# 4-Flowmeter.net
KiCad netlist of a schematic drawn in EAGLE
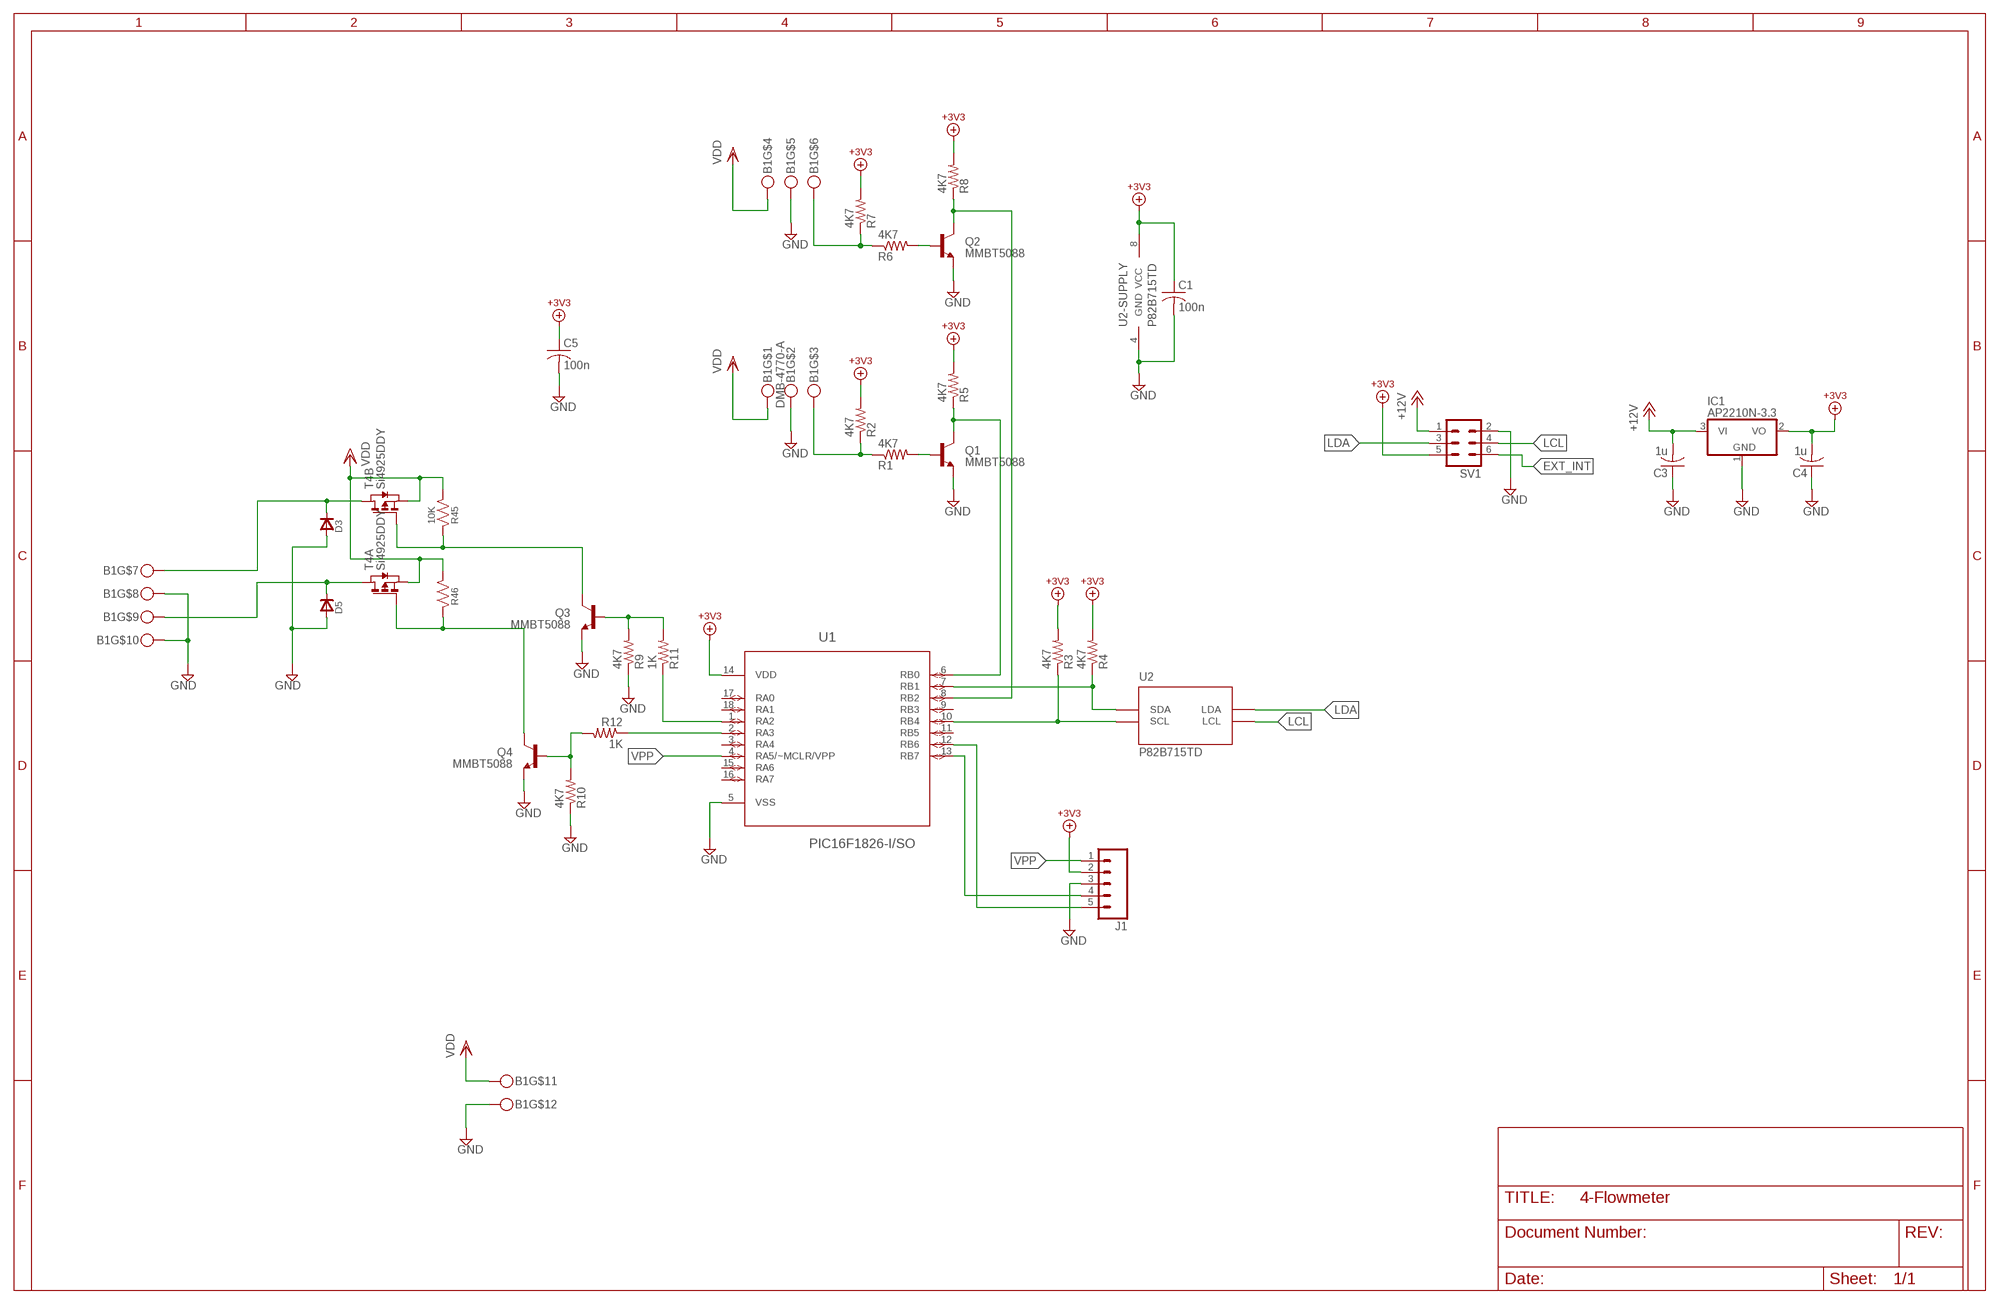
[diagram p0: schematic, sheet 1]

(export (version "E")
  (design (tool "Eeschema 10.0.6"))
  (components
    (comp (ref "B1")
      (value "DMB-4770-A")
      (footprint "eagle-import:DMB-4770-A-PKG")
      (libsource (lib "eagle-import") (part "DMB-4770-A"))
    )
    (comp (ref "C1")
      (value "100n")
      (footprint "eagle-import:C0805")
      (libsource (lib "eagle-import") (part "C-USC0805"))
    )
    (comp (ref "C3")
      (value "1u")
      (footprint "eagle-import:C0805")
      (libsource (lib "eagle-import") (part "C-USC0805"))
    )
    (comp (ref "C4")
      (value "1u")
      (footprint "eagle-import:C0805")
      (libsource (lib "eagle-import") (part "C-USC0805"))
    )
    (comp (ref "C5")
      (value "100n")
      (footprint "eagle-import:C0805")
      (libsource (lib "eagle-import") (part "C-USC0805"))
    )
    (comp (ref "D3")
      (value "DSMA")
      (footprint "eagle-import:DSMA")
      (libsource (lib "eagle-import") (part "DSMA"))
    )
    (comp (ref "D5")
      (value "DSMA")
      (footprint "eagle-import:DSMA")
      (libsource (lib "eagle-import") (part "DSMA"))
    )
    (comp (ref "IC1")
      (value "AP2210N-3.3")
      (footprint "eagle-import:SOT23")
      (libsource (lib "eagle-import") (part "MCP1703CB"))
    )
    (comp (ref "J1")
      (value "M05PTH")
      (footprint "eagle-import:1X05")
      (libsource (lib "eagle-import") (part "M05PTH"))
    )
    (comp (ref "Q1")
      (value "MMBT5088")
      (footprint "eagle-import:SOT23-3")
      (libsource (lib "eagle-import") (part "TRANSISTOR_NPNMMBT5088"))
    )
    (comp (ref "Q2")
      (value "MMBT5088")
      (footprint "eagle-import:SOT23-3")
      (libsource (lib "eagle-import") (part "TRANSISTOR_NPNMMBT5088"))
    )
    (comp (ref "Q3")
      (value "MMBT5088")
      (footprint "eagle-import:SOT23-3")
      (libsource (lib "eagle-import") (part "TRANSISTOR_NPNMMBT5088"))
    )
    (comp (ref "Q4")
      (value "MMBT5088")
      (footprint "eagle-import:SOT23-3")
      (libsource (lib "eagle-import") (part "TRANSISTOR_NPNMMBT5088"))
    )
    (comp (ref "R1")
      (value "4K7")
      (footprint "eagle-import:R0805")
      (libsource (lib "eagle-import") (part "R-US_R0805"))
    )
    (comp (ref "R2")
      (value "4K7")
      (footprint "eagle-import:R0805")
      (libsource (lib "eagle-import") (part "R-US_R0805"))
    )
    (comp (ref "R3")
      (value "4K7")
      (footprint "eagle-import:R0805")
      (libsource (lib "eagle-import") (part "R-US_R0805"))
    )
    (comp (ref "R4")
      (value "4K7")
      (footprint "eagle-import:R0805")
      (libsource (lib "eagle-import") (part "R-US_R0805"))
    )
    (comp (ref "R5")
      (value "4K7")
      (footprint "eagle-import:R0805")
      (libsource (lib "eagle-import") (part "R-US_R0805"))
    )
    (comp (ref "R6")
      (value "4K7")
      (footprint "eagle-import:R0805")
      (libsource (lib "eagle-import") (part "R-US_R0805"))
    )
    (comp (ref "R7")
      (value "4K7")
      (footprint "eagle-import:R0805")
      (libsource (lib "eagle-import") (part "R-US_R0805"))
    )
    (comp (ref "R8")
      (value "4K7")
      (footprint "eagle-import:R0805")
      (libsource (lib "eagle-import") (part "R-US_R0805"))
    )
    (comp (ref "R9")
      (value "4K7")
      (footprint "eagle-import:R0805")
      (libsource (lib "eagle-import") (part "R-US_R0805"))
    )
    (comp (ref "R10")
      (value "4K7")
      (footprint "eagle-import:R0805")
      (libsource (lib "eagle-import") (part "R-US_R0805"))
    )
    (comp (ref "R11")
      (value "1K")
      (footprint "eagle-import:R0805")
      (libsource (lib "eagle-import") (part "R-US_R0805"))
    )
    (comp (ref "R12")
      (value "1K")
      (footprint "eagle-import:R0805")
      (libsource (lib "eagle-import") (part "R-US_R0805"))
    )
    (comp (ref "R45")
      (value "10K")
      (footprint "eagle-import:R0805")
      (libsource (lib "eagle-import") (part "RU0805"))
    )
    (comp (ref "R46")
      (value "RU0805")
      (footprint "eagle-import:R0805")
      (libsource (lib "eagle-import") (part "RU0805"))
    )
    (comp (ref "SV1")
      (value "ML6")
      (footprint "eagle-import:ML6")
      (libsource (lib "eagle-import") (part "ML6"))
    )
    (comp (ref "T4")
      (value "Si4925DDY")
      (footprint "eagle-import:SO8")
      (libsource (lib "eagle-import") (part "PMOS2SO8"))
    )
    (comp (ref "U1")
      (value "PIC16F1826-I/SO")
      (footprint "eagle-import:SOIC127P1030X175-18N")
      (libsource (lib "eagle-import") (part "PIC16F1826-I/SO"))
    )
    (comp (ref "U2")
      (value "P82B715TD")
      (footprint "eagle-import:SOIC-8")
      (fields (field (name "MANUFACTURER") "NXP Semiconductors") (field (name "PART_NUMBER") "P82B715TD,118"))
      (libsource (lib "eagle-import") (part "P82B715?TD"))
    )
  )
  (nets
    (net (code "1") (name "+12V") (class "Default")
      (node (ref "C3") (pin "2") (pinfunction "2_2") (pintype "passive"))
      (node (ref "IC1") (pin "3") (pinfunction "VI_3") (pintype "input"))
      (node (ref "SV1") (pin "1") (pinfunction "1_1") (pintype "passive"))
    )
    (net (code "2") (name "EXT_INT") (class "Default")
      (node (ref "SV1") (pin "6") (pinfunction "6_6") (pintype "passive"))
    )
    (net (code "3") (name "GND") (class "Default")
      (node (ref "B1") (pin "P$10") (pinfunction "KL_P$10") (pintype "passive"))
      (node (ref "B1") (pin "P$12") (pinfunction "KL_P$12") (pintype "passive"))
      (node (ref "B1") (pin "P$2") (pinfunction "KL_P$2") (pintype "passive"))
      (node (ref "B1") (pin "P$5") (pinfunction "KL_P$5") (pintype "passive"))
      (node (ref "B1") (pin "P$8") (pinfunction "KL_P$8") (pintype "passive"))
      (node (ref "C1") (pin "2") (pinfunction "2_2") (pintype "passive"))
      (node (ref "C3") (pin "1") (pinfunction "1_1") (pintype "passive"))
      (node (ref "C4") (pin "1") (pinfunction "1_1") (pintype "passive"))
      (node (ref "C5") (pin "2") (pinfunction "2_2") (pintype "passive"))
      (node (ref "D3") (pin "A") (pinfunction "A_A") (pintype "passive"))
      (node (ref "D5") (pin "A") (pinfunction "A_A") (pintype "passive"))
      (node (ref "IC1") (pin "1") (pinfunction "GND_1") (pintype "passive"))
      (node (ref "J1") (pin "3") (pinfunction "3_3") (pintype "passive"))
      (node (ref "Q1") (pin "2") (pinfunction "E_2") (pintype "passive"))
      (node (ref "Q2") (pin "2") (pinfunction "E_2") (pintype "passive"))
      (node (ref "Q3") (pin "2") (pinfunction "E_2") (pintype "passive"))
      (node (ref "Q4") (pin "2") (pinfunction "E_2") (pintype "passive"))
      (node (ref "R10") (pin "1") (pinfunction "1_1") (pintype "passive"))
      (node (ref "R9") (pin "1") (pinfunction "1_1") (pintype "passive"))
      (node (ref "SV1") (pin "2") (pinfunction "2_2") (pintype "passive"))
      (node (ref "U1") (pin "5") (pinfunction "VSS_5") (pintype "power_in"))
      (node (ref "U2") (pin "4") (pinfunction "GND_4") (pintype "bidirectional"))
    )
    (net (code "4") (name "LCL") (class "Default")
      (node (ref "SV1") (pin "4") (pinfunction "4_4") (pintype "passive"))
      (node (ref "U2") (pin "2") (pinfunction "LCL_2") (pintype "bidirectional"))
    )
    (net (code "5") (name "LDA") (class "Default")
      (node (ref "SV1") (pin "3") (pinfunction "3_3") (pintype "passive"))
      (node (ref "U2") (pin "7") (pinfunction "LDA_7") (pintype "bidirectional"))
    )
    (net (code "6") (name "Net-(B1F-KL)") (class "Default")
      (node (ref "B1") (pin "P$3") (pinfunction "KL_P$3") (pintype "passive"))
      (node (ref "R1") (pin "1") (pinfunction "1_1") (pintype "passive"))
      (node (ref "R2") (pin "1") (pinfunction "1_1") (pintype "passive"))
    )
    (net (code "7") (name "Net-(B1I-KL)") (class "Default")
      (node (ref "B1") (pin "P$6") (pinfunction "KL_P$6") (pintype "passive"))
      (node (ref "R6") (pin "1") (pinfunction "1_1") (pintype "passive"))
      (node (ref "R7") (pin "1") (pinfunction "1_1") (pintype "passive"))
    )
    (net (code "8") (name "Net-(B1J-KL)") (class "Default")
      (node (ref "B1") (pin "P$7") (pinfunction "KL_P$7") (pintype "passive"))
      (node (ref "D3") (pin "C") (pinfunction "C_C") (pintype "passive"))
      (node (ref "T4") (pin "5") (pinfunction "D_5") (pintype "passive"))
      (node (ref "T4") (pin "6") (pinfunction "D_6") (pintype "passive"))
    )
    (net (code "9") (name "Net-(B1L-KL)") (class "Default")
      (node (ref "B1") (pin "P$9") (pinfunction "KL_P$9") (pintype "passive"))
      (node (ref "D5") (pin "C") (pinfunction "C_C") (pintype "passive"))
      (node (ref "T4") (pin "7") (pinfunction "D_7") (pintype "passive"))
      (node (ref "T4") (pin "8") (pinfunction "D_8") (pintype "passive"))
    )
    (net (code "10") (name "Net-(Q1-B)") (class "Default")
      (node (ref "Q1") (pin "1") (pinfunction "B_1") (pintype "passive"))
      (node (ref "R1") (pin "2") (pinfunction "2_2") (pintype "passive"))
    )
    (net (code "11") (name "Net-(Q1-C)") (class "Default")
      (node (ref "Q1") (pin "3") (pinfunction "C_3") (pintype "passive"))
      (node (ref "R5") (pin "1") (pinfunction "1_1") (pintype "passive"))
      (node (ref "U1") (pin "6") (pinfunction "RB0_6") (pintype "bidirectional"))
    )
    (net (code "12") (name "Net-(Q2-B)") (class "Default")
      (node (ref "Q2") (pin "1") (pinfunction "B_1") (pintype "passive"))
      (node (ref "R6") (pin "2") (pinfunction "2_2") (pintype "passive"))
    )
    (net (code "13") (name "Net-(Q2-C)") (class "Default")
      (node (ref "Q2") (pin "3") (pinfunction "C_3") (pintype "passive"))
      (node (ref "R8") (pin "1") (pinfunction "1_1") (pintype "passive"))
      (node (ref "U1") (pin "8") (pinfunction "RB2_8") (pintype "bidirectional"))
    )
    (net (code "14") (name "Net-(Q3-B)") (class "Default")
      (node (ref "Q3") (pin "1") (pinfunction "B_1") (pintype "passive"))
      (node (ref "R11") (pin "2") (pinfunction "2_2") (pintype "passive"))
      (node (ref "R9") (pin "2") (pinfunction "2_2") (pintype "passive"))
    )
    (net (code "15") (name "Net-(Q3-C)") (class "Default")
      (node (ref "Q3") (pin "3") (pinfunction "C_3") (pintype "passive"))
      (node (ref "R45") (pin "1") (pinfunction "1_1") (pintype "passive"))
      (node (ref "T4") (pin "4") (pinfunction "G_4") (pintype "passive"))
    )
    (net (code "16") (name "Net-(Q4-B)") (class "Default")
      (node (ref "Q4") (pin "1") (pinfunction "B_1") (pintype "passive"))
      (node (ref "R10") (pin "2") (pinfunction "2_2") (pintype "passive"))
      (node (ref "R12") (pin "2") (pinfunction "2_2") (pintype "passive"))
    )
    (net (code "17") (name "Net-(Q4-C)") (class "Default")
      (node (ref "Q4") (pin "3") (pinfunction "C_3") (pintype "passive"))
      (node (ref "R46") (pin "1") (pinfunction "1_1") (pintype "passive"))
      (node (ref "T4") (pin "2") (pinfunction "G_2") (pintype "passive"))
    )
    (net (code "18") (name "Net-(U1-RA2)") (class "Default")
      (node (ref "R11") (pin "1") (pinfunction "1_1") (pintype "passive"))
      (node (ref "U1") (pin "1") (pinfunction "RA2_1") (pintype "bidirectional"))
    )
    (net (code "19") (name "Net-(U1-RA3)") (class "Default")
      (node (ref "R12") (pin "1") (pinfunction "1_1") (pintype "passive"))
      (node (ref "U1") (pin "2") (pinfunction "RA3_2") (pintype "bidirectional"))
    )
    (net (code "20") (name "Net-(U1-RB1)") (class "Default")
      (node (ref "R4") (pin "1") (pinfunction "1_1") (pintype "passive"))
      (node (ref "U1") (pin "7") (pinfunction "RB1_7") (pintype "bidirectional"))
      (node (ref "U2") (pin "6") (pinfunction "SDA_6") (pintype "bidirectional"))
    )
    (net (code "21") (name "Net-(U1-RB4)") (class "Default")
      (node (ref "R3") (pin "1") (pinfunction "1_1") (pintype "passive"))
      (node (ref "U1") (pin "10") (pinfunction "RB4_10") (pintype "bidirectional"))
      (node (ref "U2") (pin "3") (pinfunction "SCL_3") (pintype "bidirectional"))
    )
    (net (code "22") (name "Net-(U1-RB6)") (class "Default")
      (node (ref "J1") (pin "5") (pinfunction "5_5") (pintype "passive"))
      (node (ref "U1") (pin "12") (pinfunction "RB6_12") (pintype "bidirectional"))
    )
    (net (code "23") (name "Net-(U1-RB7)") (class "Default")
      (node (ref "J1") (pin "4") (pinfunction "4_4") (pintype "passive"))
      (node (ref "U1") (pin "13") (pinfunction "RB7_13") (pintype "bidirectional"))
    )
    (net (code "24") (name "V+3V3") (class "Default")
      (node (ref "C1") (pin "1") (pinfunction "1_1") (pintype "passive"))
      (node (ref "C4") (pin "2") (pinfunction "2_2") (pintype "passive"))
      (node (ref "C5") (pin "1") (pinfunction "1_1") (pintype "passive"))
      (node (ref "IC1") (pin "2") (pinfunction "VO_2") (pintype "passive"))
      (node (ref "J1") (pin "2") (pinfunction "2_2") (pintype "passive"))
      (node (ref "R2") (pin "2") (pinfunction "2_2") (pintype "passive"))
      (node (ref "R3") (pin "2") (pinfunction "2_2") (pintype "passive"))
      (node (ref "R4") (pin "2") (pinfunction "2_2") (pintype "passive"))
      (node (ref "R5") (pin "2") (pinfunction "2_2") (pintype "passive"))
      (node (ref "R7") (pin "2") (pinfunction "2_2") (pintype "passive"))
      (node (ref "R8") (pin "2") (pinfunction "2_2") (pintype "passive"))
      (node (ref "SV1") (pin "5") (pinfunction "5_5") (pintype "passive"))
      (node (ref "U1") (pin "14") (pinfunction "VDD_14") (pintype "power_in"))
      (node (ref "U2") (pin "8") (pinfunction "VCC_8") (pintype "bidirectional"))
    )
    (net (code "25") (name "VDD") (class "Default")
      (node (ref "B1") (pin "P$1") (pinfunction "KL_P$1") (pintype "passive"))
      (node (ref "B1") (pin "P$11") (pinfunction "KL_P$11") (pintype "passive"))
      (node (ref "B1") (pin "P$4") (pinfunction "KL_P$4") (pintype "passive"))
      (node (ref "R45") (pin "2") (pinfunction "2_2") (pintype "passive"))
      (node (ref "R46") (pin "2") (pinfunction "2_2") (pintype "passive"))
      (node (ref "T4") (pin "1") (pinfunction "S_1") (pintype "passive"))
      (node (ref "T4") (pin "3") (pinfunction "S_3") (pintype "passive"))
    )
    (net (code "26") (name "VPP") (class "Default")
      (node (ref "J1") (pin "1") (pinfunction "1_1") (pintype "passive"))
      (node (ref "U1") (pin "4") (pinfunction "RA5/~{MCLR/VPP}_4") (pintype "bidirectional"))
    )
    (net (code "27") (name "unconnected-(U1-RA0-Pad17)") (class "Default")
      (node (ref "U1") (pin "17") (pinfunction "RA0_17") (pintype "bidirectional"))
    )
    (net (code "28") (name "unconnected-(U1-RA1-Pad18)") (class "Default")
      (node (ref "U1") (pin "18") (pinfunction "RA1_18") (pintype "bidirectional"))
    )
    (net (code "29") (name "unconnected-(U1-RA4-Pad3)") (class "Default")
      (node (ref "U1") (pin "3") (pinfunction "RA4_3") (pintype "bidirectional"))
    )
    (net (code "30") (name "unconnected-(U1-RA6-Pad15)") (class "Default")
      (node (ref "U1") (pin "15") (pinfunction "RA6_15") (pintype "bidirectional"))
    )
    (net (code "31") (name "unconnected-(U1-RA7-Pad16)") (class "Default")
      (node (ref "U1") (pin "16") (pinfunction "RA7_16") (pintype "bidirectional"))
    )
    (net (code "32") (name "unconnected-(U1-RB3-Pad9)") (class "Default")
      (node (ref "U1") (pin "9") (pinfunction "RB3_9") (pintype "bidirectional"))
    )
    (net (code "33") (name "unconnected-(U1-RB5-Pad11)") (class "Default")
      (node (ref "U1") (pin "11") (pinfunction "RB5_11") (pintype "bidirectional"))
    )
  )
)
